# Side_1.net
KiCad netlist of a schematic drawn in EAGLE
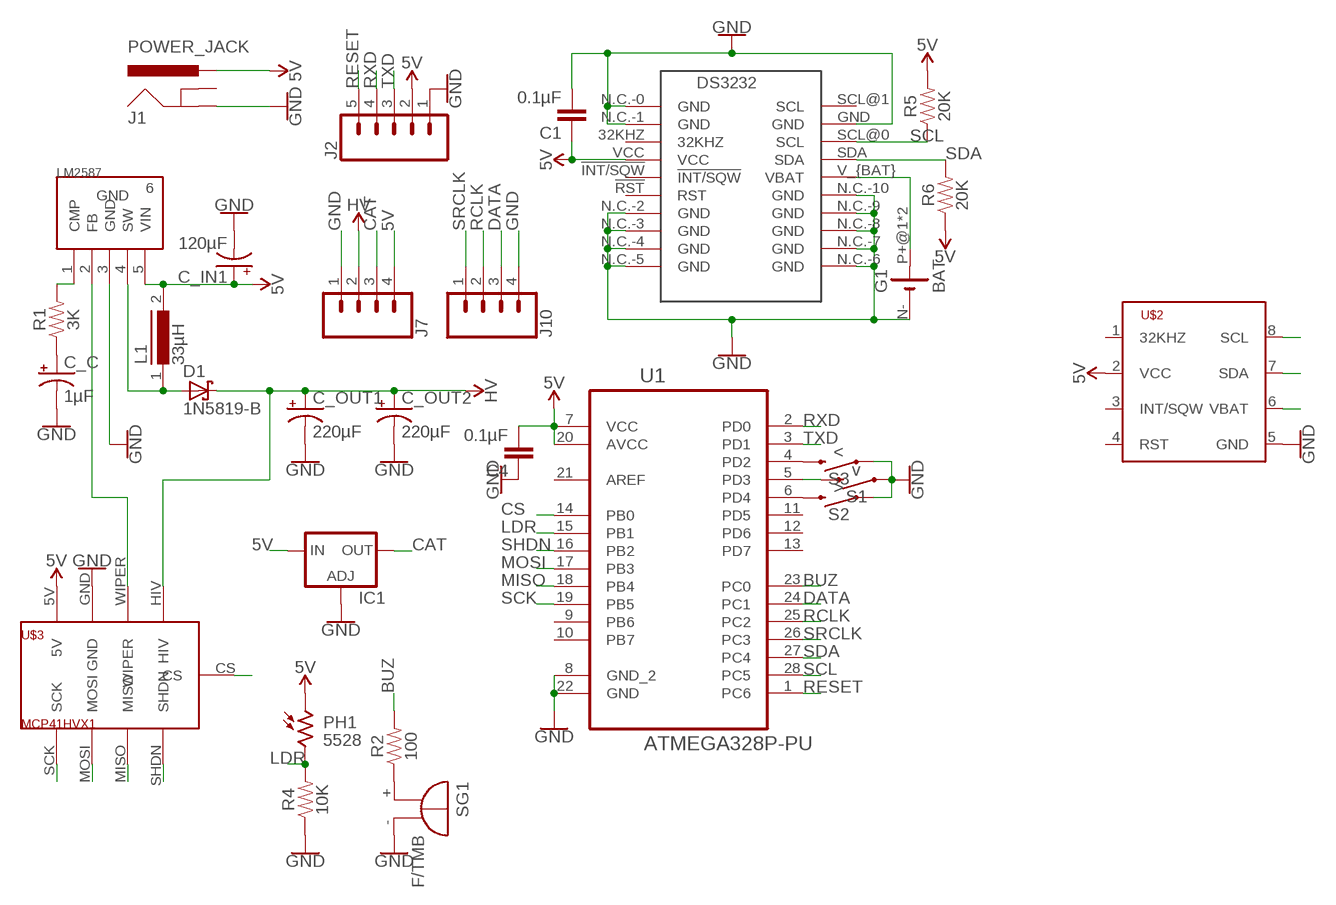
[diagram p0: schematic, sheet 1]

(export (version "E")
  (design (tool "Eeschema 10.0.6"))
  (components
    (comp (ref "C1")
      (value "0.1µF")
      (footprint "eagle-import:CAP-0.1I")
      (libsource (lib "eagle-import") (part "0.1µF-0.1''"))
    )
    (comp (ref "C4")
      (value "0.1µF")
      (footprint "eagle-import:CAP-0.1I")
      (libsource (lib "eagle-import") (part "0.1µF-0.1''"))
    )
    (comp (ref "C_C")
      (value "1µF")
      (footprint "eagle-import:CAP_POL_2MM")
      (libsource (lib "eagle-import") (part "CAP_POL_1µF"))
    )
    (comp (ref "C_IN1")
      (value "120µF")
      (footprint "eagle-import:CAP_POL_3MM")
      (libsource (lib "eagle-import") (part "CAP_POL_120µF"))
    )
    (comp (ref "C_OUT1")
      (value "220µF")
      (footprint "eagle-import:CPOL-RADIAL-5MM-10MM")
      (libsource (lib "eagle-import") (part "1000UF-RADIAL-5MM-25V-20%"))
    )
    (comp (ref "C_OUT2")
      (value "220µF")
      (footprint "eagle-import:CPOL-RADIAL-5MM-10MM")
      (libsource (lib "eagle-import") (part "1000UF-RADIAL-5MM-25V-20%"))
    )
    (comp (ref "D1")
      (value "1N5819-B")
      (footprint "eagle-import:DO41-7.6")
      (libsource (lib "eagle-import") (part "1N5819-B"))
    )
    (comp (ref "G1")
      (value "BAT")
      (footprint "eagle-import:CELL_RETAINER_11.6MM")
      (fields (field (name "MF") "KEYSTONE") (field (name "MPN") "2997"))
      (libsource (lib "eagle-import") (part "BATTERY-HOLDER_11.6MM"))
    )
    (comp (ref "IC1")
      (value "LM317TS")
      (footprint "eagle-import:317TS")
      (libsource (lib "eagle-import") (part "LM317TS"))
    )
    (comp (ref "J1")
      (value "POWER_JACK")
      (footprint "eagle-import:POWER_JACK_PTH")
      (libsource (lib "eagle-import") (part "POWER_JACK"))
    )
    (comp (ref "J2")
      (value "CONN_05")
      (footprint "eagle-import:1X05")
      (libsource (lib "eagle-import") (part "CONN_05"))
    )
    (comp (ref "J7")
      (value "CONN_04")
      (footprint "eagle-import:1X04")
      (libsource (lib "eagle-import") (part "CONN_04"))
    )
    (comp (ref "J10")
      (value "CONN_04")
      (footprint "eagle-import:1X04")
      (libsource (lib "eagle-import") (part "CONN_04"))
    )
    (comp (ref "L1")
      (value "33µH")
      (footprint "eagle-import:MICC12")
      (libsource (lib "eagle-import") (part "MICC12"))
    )
    (comp (ref "LM2587")
      (value "LM2587S")
      (footprint "eagle-import:TO263-5")
      (libsource (lib "eagle-import") (part "LM2587S"))
    )
    (comp (ref "PH1")
      (value "5528")
      (footprint "eagle-import:5528")
      (libsource (lib "eagle-import") (part "5528"))
    )
    (comp (ref "R1")
      (value "3K")
      (footprint "eagle-import:AXIAL-0.3")
      (libsource (lib "eagle-import") (part "RESISTORAXIAL-0.3"))
    )
    (comp (ref "R2")
      (value "100")
      (footprint "eagle-import:AXIAL-0.3")
      (libsource (lib "eagle-import") (part "RESISTORAXIAL-0.3"))
    )
    (comp (ref "R4")
      (value "10K")
      (footprint "eagle-import:AXIAL-0.3")
      (libsource (lib "eagle-import") (part "RESISTORAXIAL-0.3"))
    )
    (comp (ref "R5")
      (value "20K")
      (footprint "eagle-import:AXIAL-0.3")
      (libsource (lib "eagle-import") (part "RESISTORAXIAL-0.3"))
    )
    (comp (ref "R6")
      (value "20K")
      (footprint "eagle-import:AXIAL-0.3")
      (libsource (lib "eagle-import") (part "RESISTORAXIAL-0.3"))
    )
    (comp (ref "S1")
      (value "v")
      (footprint "eagle-import:TACTILE_SWITCH_PTH_6.0MM")
      (libsource (lib "eagle-import") (part "MOMENTARY-SWITCH-SPST-PTH-6.0MM"))
    )
    (comp (ref "S2")
      (value ">")
      (footprint "eagle-import:TACTILE_SWITCH_PTH_6.0MM")
      (libsource (lib "eagle-import") (part "MOMENTARY-SWITCH-SPST-PTH-6.0MM"))
    )
    (comp (ref "S3")
      (value "<")
      (footprint "eagle-import:TACTILE_SWITCH_PTH_6.0MM")
      (libsource (lib "eagle-import") (part "MOMENTARY-SWITCH-SPST-PTH-6.0MM"))
    )
    (comp (ref "SG1")
      (value "F/TMB")
      (footprint "eagle-import:F_TMB")
      (libsource (lib "eagle-import") (part "F/TMB"))
    )
    (comp (ref "U$1")
      (value "DS3232")
      (footprint "eagle-import:SO20-2")
      (libsource (lib "eagle-import") (part "DS3232"))
    )
    (comp (ref "U$2")
      (value "DS3232M")
      (footprint "eagle-import:SO8")
      (libsource (lib "eagle-import") (part "DS3232M"))
    )
    (comp (ref "U$3")
      (value "MCP41HVX1")
      (footprint "eagle-import:MCP41HVX1_BREAKOUT")
      (libsource (lib "eagle-import") (part "MCP41HVX1_BREAKOUT"))
    )
    (comp (ref "U1")
      (value "ATMEGA328P-PU")
      (footprint "eagle-import:DIP254P762X457-28")
      (libsource (lib "eagle-import") (part "ATMEGA328P-PU"))
    )
  )
  (nets
    (net (code "1") (name "/BAT") (class "Default")
      (node (ref "G1") (pin "P+@1") (pinfunction "+_P+@1") (pintype "passive"))
      (node (ref "G1") (pin "P+@2") (pinfunction "+_P+@2") (pintype "passive"))
      (node (ref "U$1") (pin "V_{BAT}") (pinfunction "VBAT_V_{BAT}") (pintype "bidirectional"))
      (node (ref "U$2") (pin "6") (pinfunction "VBAT_6") (pintype "bidirectional"))
    )
    (net (code "2") (name "/BUZ") (class "Default")
      (node (ref "R2") (pin "P$2") (pinfunction "2_P$2") (pintype "passive"))
      (node (ref "U1") (pin "23") (pinfunction "PC0_23") (pintype "bidirectional"))
    )
    (net (code "3") (name "/CAT") (class "Default")
      (node (ref "IC1") (pin "2") (pinfunction "OUT_2") (pintype "passive"))
      (node (ref "J7") (pin "3") (pinfunction "3_3") (pintype "passive"))
    )
    (net (code "4") (name "/CS") (class "Default")
      (node (ref "U$3") (pin "CS") (pinfunction "CS_CS") (pintype "bidirectional"))
      (node (ref "U1") (pin "14") (pinfunction "PB0_14") (pintype "bidirectional"))
    )
    (net (code "5") (name "/DATA") (class "Default")
      (node (ref "J10") (pin "3") (pinfunction "3_3") (pintype "passive"))
      (node (ref "U1") (pin "24") (pinfunction "PC1_24") (pintype "bidirectional"))
    )
    (net (code "6") (name "/LDR") (class "Default")
      (node (ref "PH1") (pin "2") (pinfunction "2_2") (pintype "passive"))
      (node (ref "R4") (pin "P$2") (pinfunction "2_P$2") (pintype "passive"))
      (node (ref "U1") (pin "15") (pinfunction "PB1_15") (pintype "bidirectional"))
    )
    (net (code "7") (name "/MISO") (class "Default")
      (node (ref "U$3") (pin "MISO") (pinfunction "MISO_MISO") (pintype "bidirectional"))
      (node (ref "U1") (pin "18") (pinfunction "PB4_18") (pintype "bidirectional"))
    )
    (net (code "8") (name "/MOSI") (class "Default")
      (node (ref "U$3") (pin "MOSI") (pinfunction "MOSI_MOSI") (pintype "bidirectional"))
      (node (ref "U1") (pin "17") (pinfunction "PB3_17") (pintype "bidirectional"))
    )
    (net (code "9") (name "/RCLK") (class "Default")
      (node (ref "J10") (pin "2") (pinfunction "2_2") (pintype "passive"))
      (node (ref "U1") (pin "25") (pinfunction "PC2_25") (pintype "bidirectional"))
    )
    (net (code "10") (name "/RESET") (class "Default")
      (node (ref "J2") (pin "5") (pinfunction "5_5") (pintype "passive"))
      (node (ref "U1") (pin "1") (pinfunction "PC6_1") (pintype "bidirectional"))
    )
    (net (code "11") (name "/RXD") (class "Default")
      (node (ref "J2") (pin "4") (pinfunction "4_4") (pintype "passive"))
      (node (ref "U1") (pin "2") (pinfunction "PD0_2") (pintype "bidirectional"))
    )
    (net (code "12") (name "/SCK") (class "Default")
      (node (ref "U$3") (pin "SCK") (pinfunction "SCK_SCK") (pintype "bidirectional"))
      (node (ref "U1") (pin "19") (pinfunction "PB5_19") (pintype "bidirectional"))
    )
    (net (code "13") (name "/SCL") (class "Default")
      (node (ref "R5") (pin "P$1") (pinfunction "1_P$1") (pintype "passive"))
      (node (ref "U$1") (pin "SCL@0") (pinfunction "SCL_SCL@0") (pintype "bidirectional"))
      (node (ref "U$2") (pin "8") (pinfunction "SCL_8") (pintype "bidirectional"))
      (node (ref "U1") (pin "28") (pinfunction "PC5_28") (pintype "bidirectional"))
    )
    (net (code "14") (name "/SDA") (class "Default")
      (node (ref "R6") (pin "P$2") (pinfunction "2_P$2") (pintype "passive"))
      (node (ref "U$1") (pin "SDA") (pinfunction "SDA_SDA") (pintype "bidirectional"))
      (node (ref "U$2") (pin "7") (pinfunction "SDA_7") (pintype "bidirectional"))
      (node (ref "U1") (pin "27") (pinfunction "PC4_27") (pintype "bidirectional"))
    )
    (net (code "15") (name "/SHDN") (class "Default")
      (node (ref "U$3") (pin "SHDN") (pinfunction "SHDN_SHDN") (pintype "bidirectional"))
      (node (ref "U1") (pin "16") (pinfunction "PB2_16") (pintype "bidirectional"))
    )
    (net (code "16") (name "/SRCLK") (class "Default")
      (node (ref "J10") (pin "1") (pinfunction "1_1") (pintype "passive"))
      (node (ref "U1") (pin "26") (pinfunction "PC3_26") (pintype "bidirectional"))
    )
    (net (code "17") (name "/TXD") (class "Default")
      (node (ref "J2") (pin "3") (pinfunction "3_3") (pintype "passive"))
      (node (ref "U1") (pin "3") (pinfunction "PD1_3") (pintype "bidirectional"))
    )
    (net (code "18") (name "5V") (class "Default")
      (node (ref "C1") (pin "1") (pinfunction "1_1") (pintype "passive"))
      (node (ref "C4") (pin "2") (pinfunction "2_2") (pintype "passive"))
      (node (ref "C_IN1") (pin "POS") (pinfunction "+_POS") (pintype "passive"))
      (node (ref "IC1") (pin "3") (pinfunction "IN_3") (pintype "input"))
      (node (ref "J1") (pin "PWR") (pinfunction "PWR_PWR") (pintype "bidirectional"))
      (node (ref "J2") (pin "2") (pinfunction "2_2") (pintype "passive"))
      (node (ref "J7") (pin "4") (pinfunction "4_4") (pintype "passive"))
      (node (ref "L1") (pin "2") (pinfunction "2_2") (pintype "passive"))
      (node (ref "LM2587") (pin "5") (pinfunction "VIN_5") (pintype "bidirectional"))
      (node (ref "PH1") (pin "1") (pinfunction "1_1") (pintype "passive"))
      (node (ref "R5") (pin "P$2") (pinfunction "2_P$2") (pintype "passive"))
      (node (ref "R6") (pin "P$1") (pinfunction "1_P$1") (pintype "passive"))
      (node (ref "U$1") (pin "VCC") (pinfunction "VCC_VCC") (pintype "bidirectional"))
      (node (ref "U$2") (pin "2") (pinfunction "VCC_2") (pintype "bidirectional"))
      (node (ref "U$3") (pin "5V") (pinfunction "5V_5V") (pintype "bidirectional"))
      (node (ref "U1") (pin "20") (pinfunction "AVCC_20") (pintype "power_in"))
      (node (ref "U1") (pin "7") (pinfunction "VCC_7") (pintype "power_in"))
    )
    (net (code "19") (name "GND") (class "Default")
      (node (ref "C1") (pin "2") (pinfunction "2_2") (pintype "passive"))
      (node (ref "C4") (pin "1") (pinfunction "1_1") (pintype "passive"))
      (node (ref "C_C") (pin "NEG") (pinfunction "-_NEG") (pintype "passive"))
      (node (ref "C_IN1") (pin "NEG") (pinfunction "-_NEG") (pintype "passive"))
      (node (ref "C_OUT1") (pin "-") (pinfunction "-_-") (pintype "passive"))
      (node (ref "C_OUT2") (pin "-") (pinfunction "-_-") (pintype "passive"))
      (node (ref "G1") (pin "N-") (pinfunction "-_N-") (pintype "passive"))
      (node (ref "IC1") (pin "1") (pinfunction "ADJ_1") (pintype "input"))
      (node (ref "J1") (pin "GND") (pinfunction "GND_GND") (pintype "bidirectional"))
      (node (ref "J10") (pin "4") (pinfunction "4_4") (pintype "passive"))
      (node (ref "J2") (pin "1") (pinfunction "1_1") (pintype "passive"))
      (node (ref "J7") (pin "1") (pinfunction "1_1") (pintype "passive"))
      (node (ref "LM2587") (pin "3") (pinfunction "GND_3") (pintype "bidirectional"))
      (node (ref "R4") (pin "P$1") (pinfunction "1_P$1") (pintype "passive"))
      (node (ref "S1") (pin "1") (pinfunction "1_1") (pintype "passive"))
      (node (ref "S2") (pin "1") (pinfunction "1_1") (pintype "passive"))
      (node (ref "S3") (pin "1") (pinfunction "1_1") (pintype "passive"))
      (node (ref "SG1") (pin "-") (pinfunction "-_-") (pintype "passive"))
      (node (ref "U$1") (pin "GND") (pinfunction "GND_GND") (pintype "bidirectional"))
      (node (ref "U$1") (pin "N.C.-0") (pinfunction "GND_N.C.-0") (pintype "bidirectional"))
      (node (ref "U$1") (pin "N.C.-1") (pinfunction "GND_N.C.-1") (pintype "bidirectional"))
      (node (ref "U$1") (pin "N.C.-10") (pinfunction "GND_N.C.-10") (pintype "bidirectional"))
      (node (ref "U$1") (pin "N.C.-2") (pinfunction "GND_N.C.-2") (pintype "bidirectional"))
      (node (ref "U$1") (pin "N.C.-3") (pinfunction "GND_N.C.-3") (pintype "bidirectional"))
      (node (ref "U$1") (pin "N.C.-4") (pinfunction "GND_N.C.-4") (pintype "bidirectional"))
      (node (ref "U$1") (pin "N.C.-5") (pinfunction "GND_N.C.-5") (pintype "bidirectional"))
      (node (ref "U$1") (pin "N.C.-6") (pinfunction "GND_N.C.-6") (pintype "bidirectional"))
      (node (ref "U$1") (pin "N.C.-7") (pinfunction "GND_N.C.-7") (pintype "bidirectional"))
      (node (ref "U$1") (pin "N.C.-8") (pinfunction "GND_N.C.-8") (pintype "bidirectional"))
      (node (ref "U$1") (pin "N.C.-9") (pinfunction "GND_N.C.-9") (pintype "bidirectional"))
      (node (ref "U$2") (pin "5") (pinfunction "GND_5") (pintype "bidirectional"))
      (node (ref "U$3") (pin "GND") (pinfunction "GND_GND") (pintype "bidirectional"))
      (node (ref "U1") (pin "22") (pinfunction "GND_22") (pintype "passive"))
      (node (ref "U1") (pin "8") (pinfunction "GND_2_8") (pintype "passive"))
    )
    (net (code "20") (name "HV") (class "Default")
      (node (ref "C_OUT1") (pin "+") (pinfunction "+_+") (pintype "passive"))
      (node (ref "C_OUT2") (pin "+") (pinfunction "+_+") (pintype "passive"))
      (node (ref "D1") (pin "C") (pinfunction "C_C") (pintype "passive"))
      (node (ref "J7") (pin "2") (pinfunction "2_2") (pintype "passive"))
      (node (ref "U$3") (pin "HIV") (pinfunction "HIV_HIV") (pintype "bidirectional"))
    )
    (net (code "21") (name "Net-(C_C-+)") (class "Default")
      (node (ref "C_C") (pin "POS") (pinfunction "+_POS") (pintype "passive"))
      (node (ref "R1") (pin "P$1") (pinfunction "1_P$1") (pintype "passive"))
    )
    (net (code "22") (name "Net-(LM2587-CMP)") (class "Default")
      (node (ref "LM2587") (pin "1") (pinfunction "CMP_1") (pintype "bidirectional"))
      (node (ref "R1") (pin "P$2") (pinfunction "2_P$2") (pintype "passive"))
    )
    (net (code "23") (name "Net-(LM2587-FB)") (class "Default")
      (node (ref "LM2587") (pin "2") (pinfunction "FB_2") (pintype "bidirectional"))
      (node (ref "U$3") (pin "WIPER") (pinfunction "WIPER_WIPER") (pintype "bidirectional"))
    )
    (net (code "24") (name "Net-(LM2587-SW)") (class "Default")
      (node (ref "D1") (pin "A") (pinfunction "A_A") (pintype "passive"))
      (node (ref "L1") (pin "1") (pinfunction "1_1") (pintype "passive"))
      (node (ref "LM2587") (pin "4") (pinfunction "SW_4") (pintype "bidirectional"))
    )
    (net (code "25") (name "Net-(R2-1)") (class "Default")
      (node (ref "R2") (pin "P$1") (pinfunction "1_P$1") (pintype "passive"))
      (node (ref "SG1") (pin "+") (pinfunction "+_+") (pintype "passive"))
    )
    (net (code "26") (name "Net-(S1-2)") (class "Default")
      (node (ref "S1") (pin "3") (pinfunction "2_3") (pintype "passive"))
      (node (ref "U1") (pin "5") (pinfunction "PD3_5") (pintype "bidirectional"))
    )
    (net (code "27") (name "Net-(S2-2)") (class "Default")
      (node (ref "S2") (pin "3") (pinfunction "2_3") (pintype "passive"))
      (node (ref "U1") (pin "6") (pinfunction "PD4_6") (pintype "bidirectional"))
    )
    (net (code "28") (name "Net-(S3-2)") (class "Default")
      (node (ref "S3") (pin "3") (pinfunction "2_3") (pintype "passive"))
      (node (ref "U1") (pin "4") (pinfunction "PD2_4") (pintype "bidirectional"))
    )
    (net (code "29") (name "unconnected-(J1-PadGNDBREAK)") (class "Default")
      (node (ref "J1") (pin "GNDBREAK") (pinfunction "GNDBREAK_GNDBREAK") (pintype "bidirectional"))
    )
    (net (code "30") (name "unconnected-(LM2587-GND-Pad6)") (class "Default")
      (node (ref "LM2587") (pin "6") (pinfunction "GND_6") (pintype "bidirectional"))
    )
    (net (code "31") (name "unconnected-(U$1-Pad32KHZ)") (class "Default")
      (node (ref "U$1") (pin "32KHZ") (pinfunction "32KHZ_32KHZ") (pintype "bidirectional"))
    )
    (net (code "32") (name "unconnected-(U$1-RST-Pad!RST)") (class "Default")
      (node (ref "U$1") (pin "!RST") (pinfunction "RST_!RST") (pintype "bidirectional"))
    )
    (net (code "33") (name "unconnected-(U$1-SCL-PadSCL@1)") (class "Default")
      (node (ref "U$1") (pin "SCL@1") (pinfunction "SCL_SCL@1") (pintype "bidirectional"))
    )
    (net (code "34") (name "unconnected-(U$1-~{INT{slash}SQW}-Pad!INT{slash}SQW)") (class "Default")
      (node (ref "U$1") (pin "!INT/SQW") (pinfunction "~{INT/SQW}_!INT/SQW") (pintype "bidirectional"))
    )
    (net (code "35") (name "unconnected-(U$2-32KHZ-Pad1)") (class "Default")
      (node (ref "U$2") (pin "1") (pinfunction "32KHZ_1") (pintype "bidirectional"))
    )
    (net (code "36") (name "unconnected-(U$2-INT{slash}SQW-Pad3)") (class "Default")
      (node (ref "U$2") (pin "3") (pinfunction "INT/SQW_3") (pintype "bidirectional"))
    )
    (net (code "37") (name "unconnected-(U$2-RST-Pad4)") (class "Default")
      (node (ref "U$2") (pin "4") (pinfunction "RST_4") (pintype "bidirectional"))
    )
    (net (code "38") (name "unconnected-(U1-AREF-Pad21)") (class "Default")
      (node (ref "U1") (pin "21") (pinfunction "AREF_21") (pintype "input"))
    )
    (net (code "39") (name "unconnected-(U1-PB6-Pad9)") (class "Default")
      (node (ref "U1") (pin "9") (pinfunction "PB6_9") (pintype "bidirectional"))
    )
    (net (code "40") (name "unconnected-(U1-PB7-Pad10)") (class "Default")
      (node (ref "U1") (pin "10") (pinfunction "PB7_10") (pintype "bidirectional"))
    )
    (net (code "41") (name "unconnected-(U1-PD5-Pad11)") (class "Default")
      (node (ref "U1") (pin "11") (pinfunction "PD5_11") (pintype "bidirectional"))
    )
    (net (code "42") (name "unconnected-(U1-PD6-Pad12)") (class "Default")
      (node (ref "U1") (pin "12") (pinfunction "PD6_12") (pintype "bidirectional"))
    )
    (net (code "43") (name "unconnected-(U1-PD7-Pad13)") (class "Default")
      (node (ref "U1") (pin "13") (pinfunction "PD7_13") (pintype "bidirectional"))
    )
  )
)
